# LilyPad_Slide_Switch.net
KiCad netlist of a schematic drawn in EAGLE
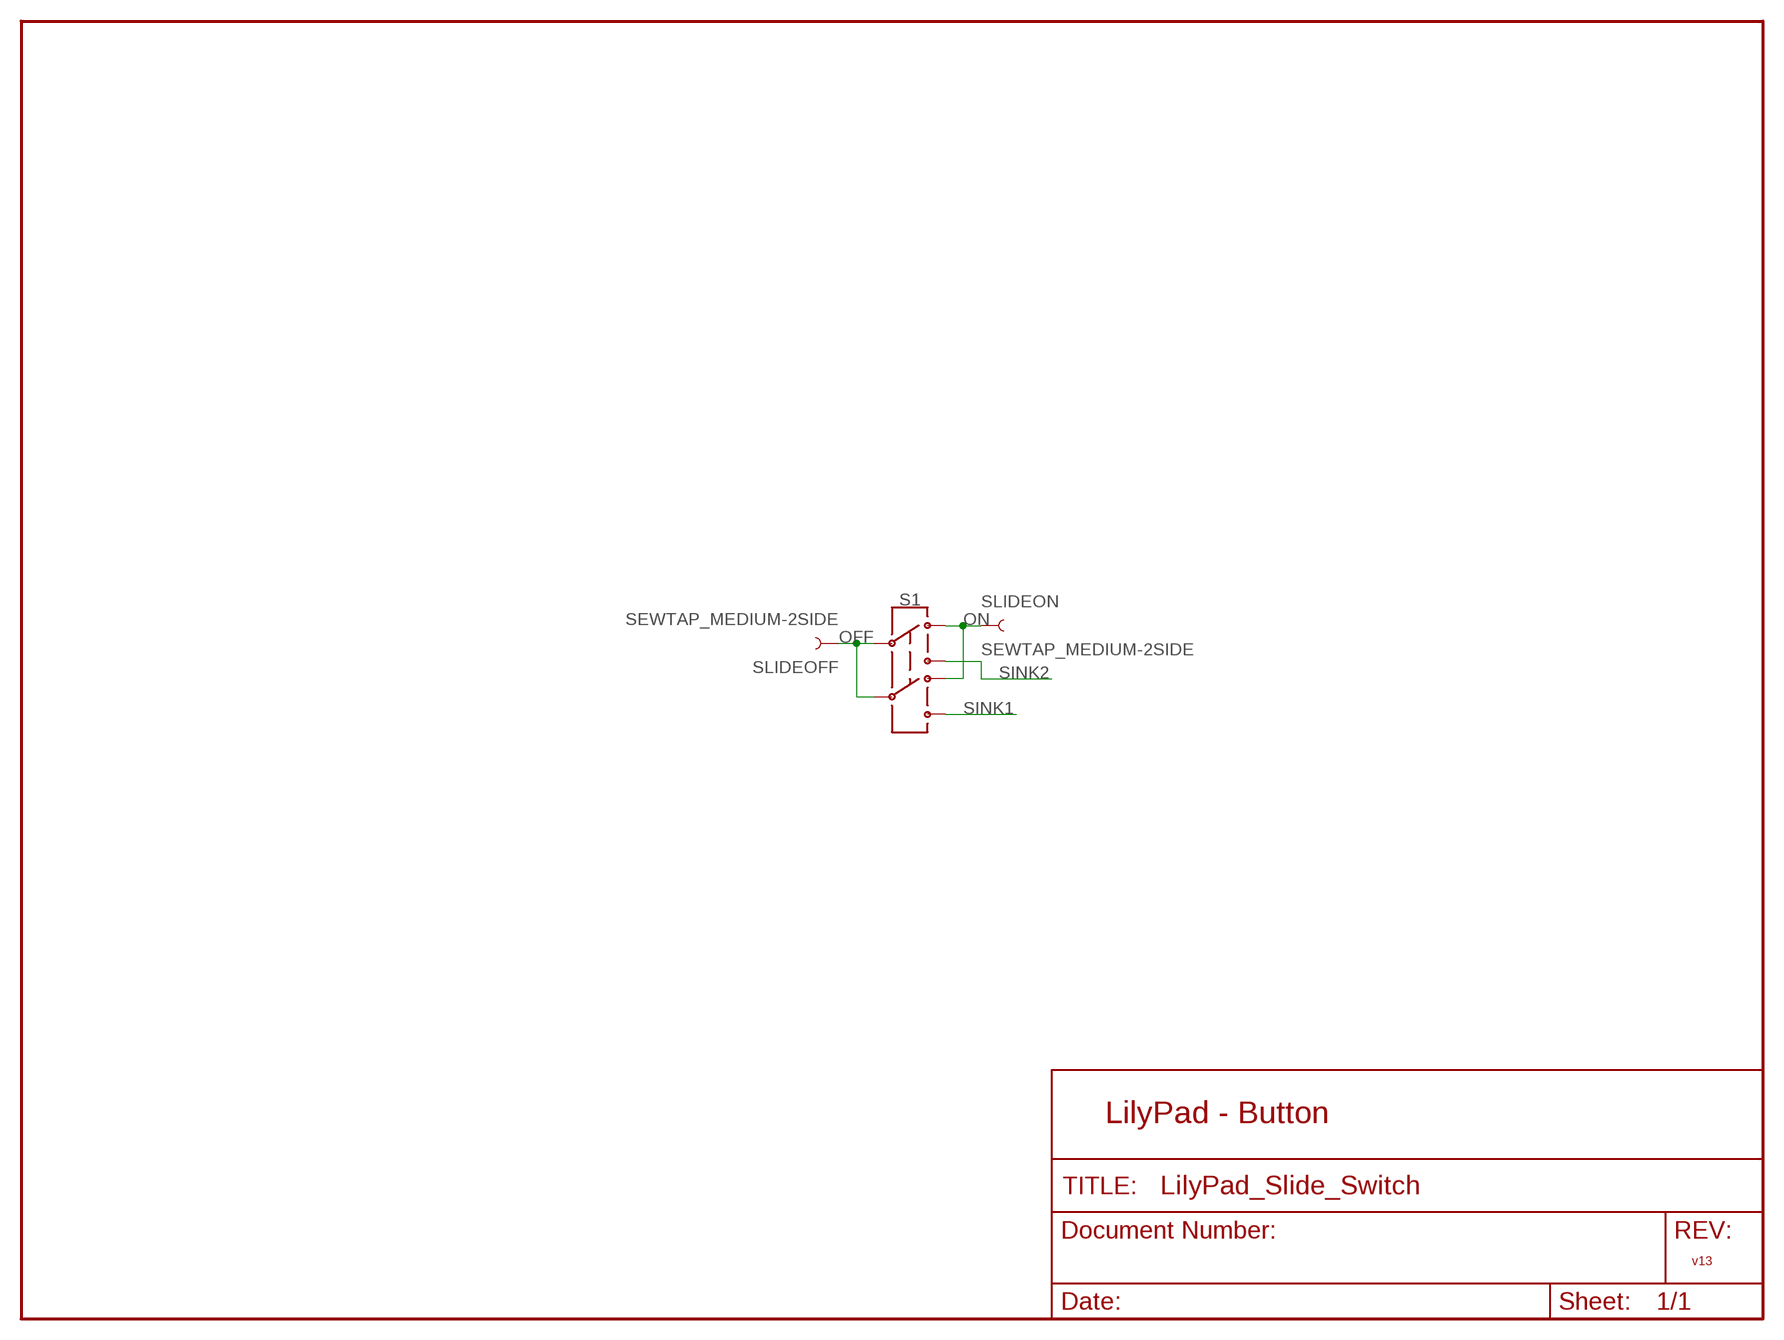
[diagram p0: schematic, sheet 1]

(export (version "E")
  (design (tool "Eeschema 10.0.6"))
  (components
    (comp (ref "S1")
      (value "SWITCH-DPDT-SMD-AYZ0202")
      (footprint "eagle-import:SWITCH_DPDT_SMD_AYZ0202")
      (libsource (lib "eagle-import") (part "SWITCH-DPDT-SMD-AYZ0202"))
    )
    (comp (ref "SLIDEOFF")
      (value "SEWTAP_MEDIUM-2SIDE")
      (footprint "eagle-import:PETAL-MEDIUM-2SIDE")
      (libsource (lib "eagle-import") (part "SEWTAP_MEDIUM-2SIDE"))
    )
    (comp (ref "SLIDEON")
      (value "SEWTAP_MEDIUM-2SIDE")
      (footprint "eagle-import:PETAL-MEDIUM-2SIDE")
      (libsource (lib "eagle-import") (part "SEWTAP_MEDIUM-2SIDE"))
    )
  )
  (nets
    (net (code "1") (name "/OFF") (class "Default")
      (node (ref "S1") (pin "2") (pinfunction "2_2") (pintype "bidirectional"))
      (node (ref "S1") (pin "5") (pinfunction "5_5") (pintype "bidirectional"))
      (node (ref "SLIDEOFF") (pin "1") (pinfunction "1_1") (pintype "bidirectional"))
    )
    (net (code "2") (name "/ON") (class "Default")
      (node (ref "S1") (pin "1") (pinfunction "1_1") (pintype "bidirectional"))
      (node (ref "S1") (pin "4") (pinfunction "4_4") (pintype "bidirectional"))
      (node (ref "SLIDEON") (pin "1") (pinfunction "1_1") (pintype "bidirectional"))
    )
    (net (code "3") (name "/SINK1") (class "Default")
      (node (ref "S1") (pin "6") (pinfunction "6_6") (pintype "bidirectional"))
    )
    (net (code "4") (name "/SINK2") (class "Default")
      (node (ref "S1") (pin "3") (pinfunction "3_3") (pintype "bidirectional"))
    )
  )
)
